# FAIO_Multiplexer.net
KiCad netlist of a schematic drawn in EAGLE
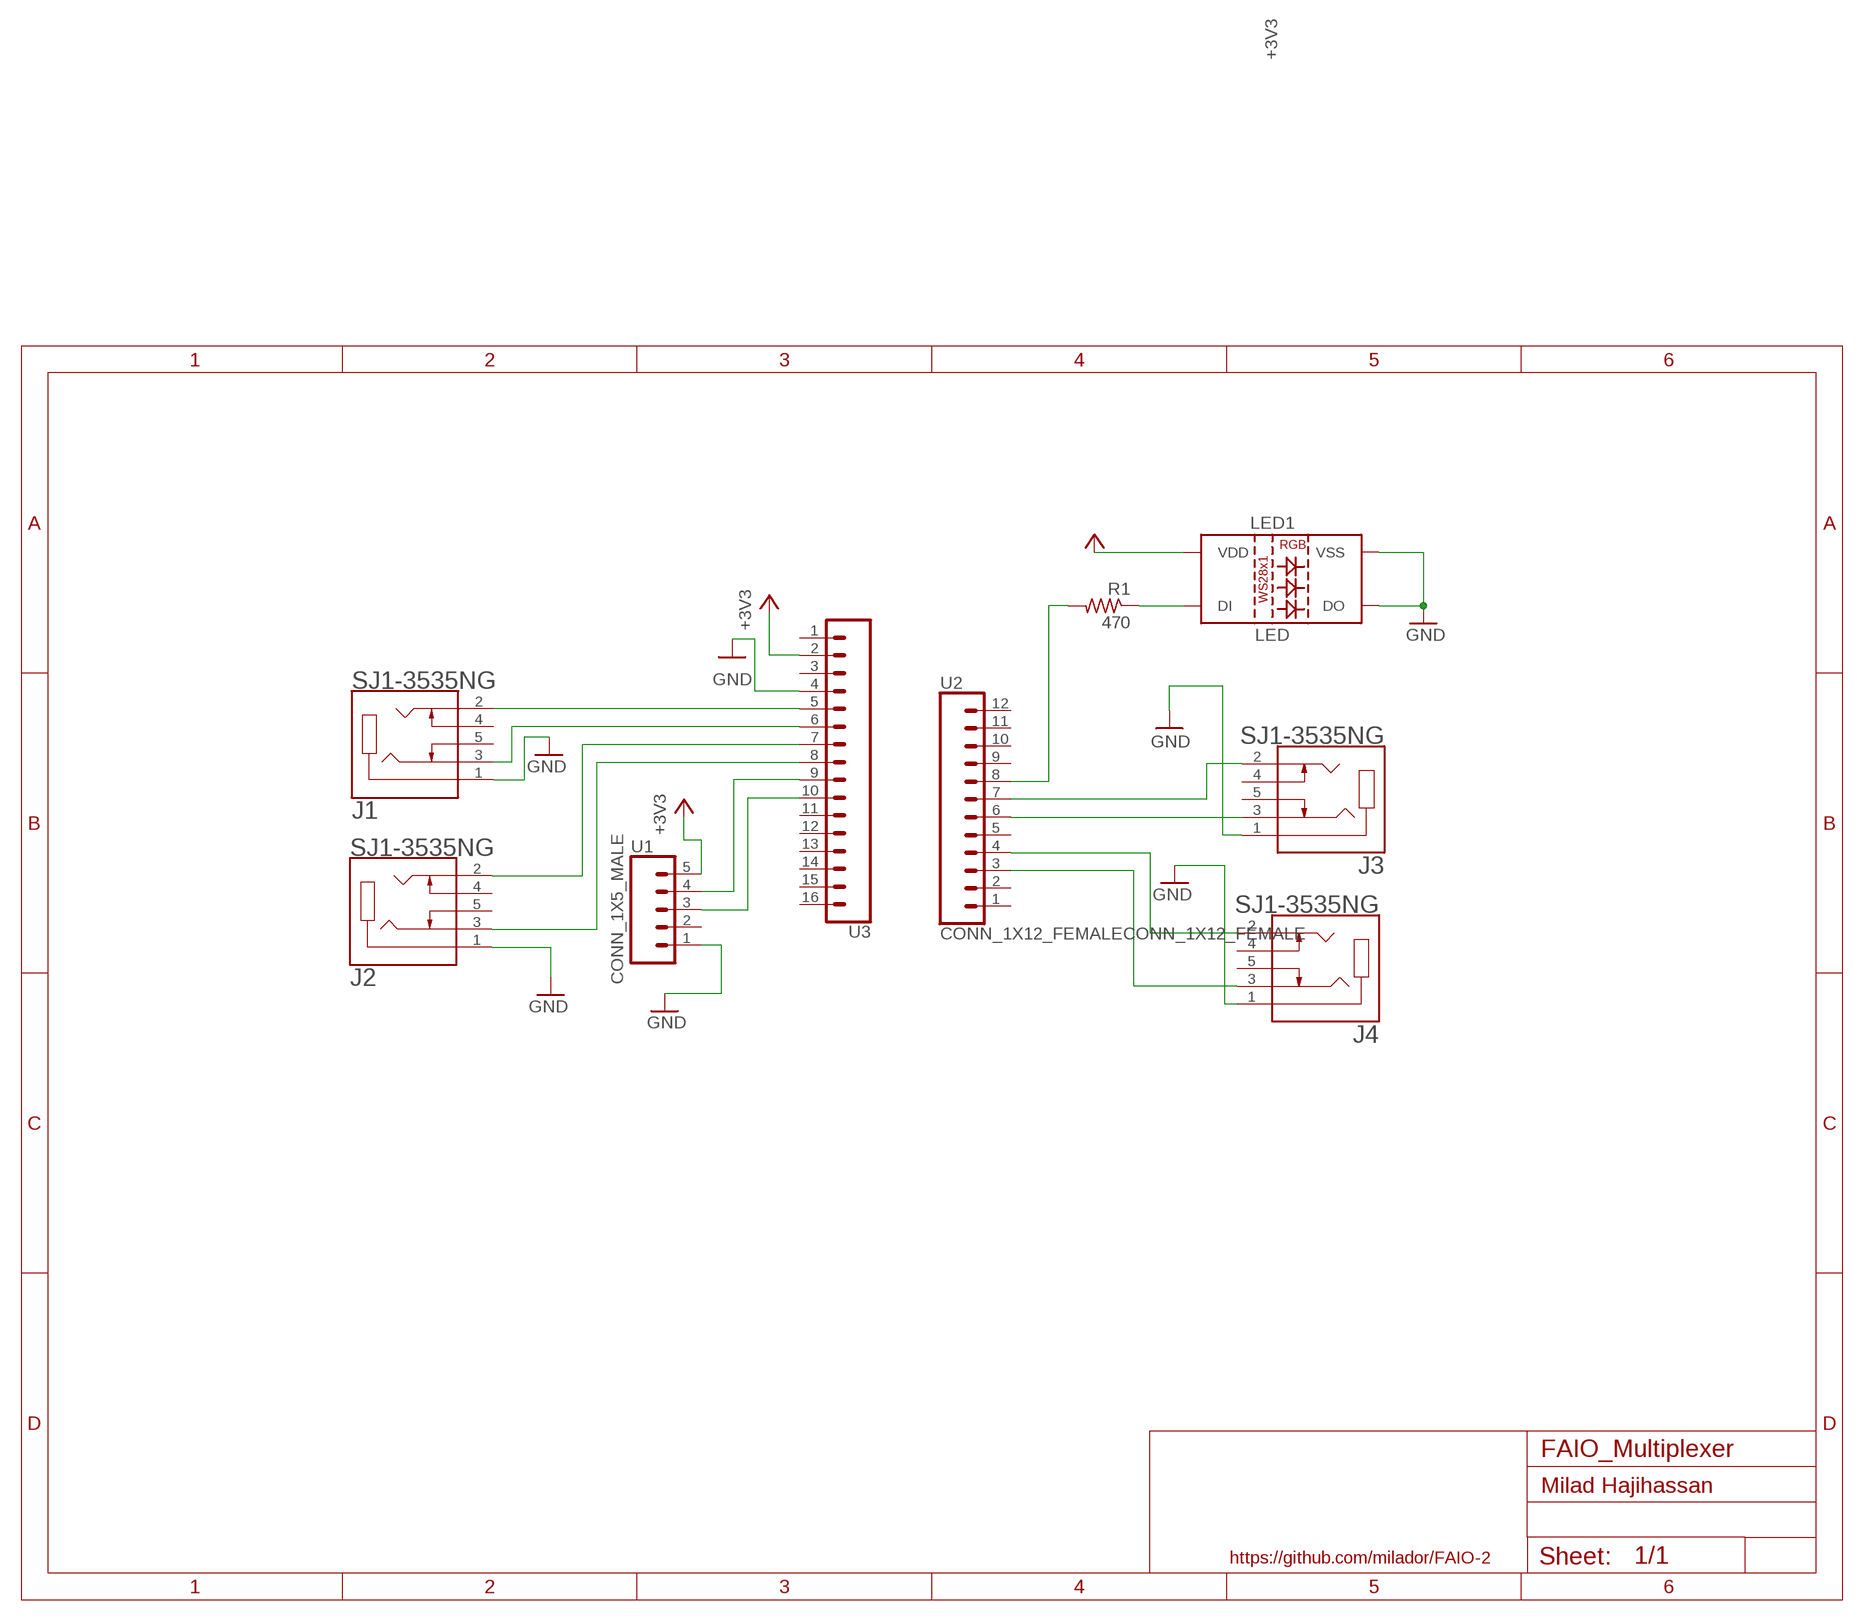
[diagram p0: schematic, sheet 1]

(export (version "E")
  (design (tool "Eeschema 10.0.6"))
  (components
    (comp (ref "J1")
      (value "SJ1-3535NG")
      (footprint "eagle-import:CUI_SJ1-3535NG")
      (fields (field (name "MANUFACTURER") "CUI"))
      (libsource (lib "eagle-import") (part "SJ1-3535NG"))
    )
    (comp (ref "J2")
      (value "SJ1-3535NG")
      (footprint "eagle-import:CUI_SJ1-3535NG")
      (fields (field (name "MANUFACTURER") "CUI"))
      (libsource (lib "eagle-import") (part "SJ1-3535NG"))
    )
    (comp (ref "J3")
      (value "SJ1-3535NG")
      (footprint "eagle-import:CUI_SJ1-3535NG")
      (fields (field (name "MANUFACTURER") "CUI"))
      (libsource (lib "eagle-import") (part "SJ1-3535NG"))
    )
    (comp (ref "J4")
      (value "SJ1-3535NG")
      (footprint "eagle-import:CUI_SJ1-3535NG")
      (fields (field (name "MANUFACTURER") "CUI"))
      (libsource (lib "eagle-import") (part "SJ1-3535NG"))
    )
    (comp (ref "LED1")
      (value "LED")
      (footprint "eagle-import:NEOPIXELS-5MM")
      (libsource (lib "eagle-import") (part "NEOPIXELS-5MM"))
    )
    (comp (ref "R1")
      (value "470")
      (footprint "eagle-import:0204_7")
      (libsource (lib "eagle-import") (part "R-US_0204/7"))
    )
    (comp (ref "U1")
      (value "CONN_1X5_MALE")
      (footprint "eagle-import:CONN_1X5")
      (libsource (lib "eagle-import") (part "CONN_1X5_MALE"))
    )
    (comp (ref "U2")
      (value "CONN_1X12_FEMALECONN_1X12_FEMALE")
      (footprint "eagle-import:CONN_1X12")
      (libsource (lib "eagle-import") (part "CONN_1X12_FEMALECONN_1X12_FEMALE"))
    )
    (comp (ref "U3")
      (value "CONN_1X16_FEMALECONN_1X16_FEMALE")
      (footprint "eagle-import:CONN_1X16")
      (libsource (lib "eagle-import") (part "CONN_1X16_FEMALECONN_1X16_FEMALE"))
    )
  )
  (nets
    (net (code "1") (name "+3V3") (class "Default")
      (node (ref "LED1") (pin "2") (pinfunction "VDD_2") (pintype "bidirectional"))
      (node (ref "U1") (pin "5") (pinfunction "5_5") (pintype "passive"))
      (node (ref "U3") (pin "2") (pinfunction "2_2") (pintype "passive"))
    )
    (net (code "2") (name "GND") (class "Default")
      (node (ref "J1") (pin "1") (pinfunction "1_1") (pintype "passive"))
      (node (ref "J2") (pin "1") (pinfunction "1_1") (pintype "passive"))
      (node (ref "J3") (pin "1") (pinfunction "1_1") (pintype "passive"))
      (node (ref "J4") (pin "1") (pinfunction "1_1") (pintype "passive"))
      (node (ref "LED1") (pin "3") (pinfunction "VSS_3") (pintype "bidirectional"))
      (node (ref "LED1") (pin "4") (pinfunction "DO_4") (pintype "bidirectional"))
      (node (ref "U1") (pin "1") (pinfunction "1_1") (pintype "passive"))
      (node (ref "U3") (pin "4") (pinfunction "4_4") (pintype "passive"))
    )
    (net (code "3") (name "Net-(J1-Pad2)") (class "Default")
      (node (ref "J1") (pin "2") (pinfunction "2_2") (pintype "passive"))
      (node (ref "U3") (pin "5") (pinfunction "5_5") (pintype "passive"))
    )
    (net (code "4") (name "Net-(J1-Pad3)") (class "Default")
      (node (ref "J1") (pin "3") (pinfunction "3_3") (pintype "passive"))
      (node (ref "U3") (pin "6") (pinfunction "6_6") (pintype "passive"))
    )
    (net (code "5") (name "Net-(J2-Pad2)") (class "Default")
      (node (ref "J2") (pin "2") (pinfunction "2_2") (pintype "passive"))
      (node (ref "U3") (pin "7") (pinfunction "7_7") (pintype "passive"))
    )
    (net (code "6") (name "Net-(J2-Pad3)") (class "Default")
      (node (ref "J2") (pin "3") (pinfunction "3_3") (pintype "passive"))
      (node (ref "U3") (pin "8") (pinfunction "8_8") (pintype "passive"))
    )
    (net (code "7") (name "Net-(J3-Pad2)") (class "Default")
      (node (ref "J3") (pin "2") (pinfunction "2_2") (pintype "passive"))
      (node (ref "U2") (pin "7") (pinfunction "7_7") (pintype "passive"))
    )
    (net (code "8") (name "Net-(J3-Pad3)") (class "Default")
      (node (ref "J3") (pin "3") (pinfunction "3_3") (pintype "passive"))
      (node (ref "U2") (pin "6") (pinfunction "6_6") (pintype "passive"))
    )
    (net (code "9") (name "Net-(J4-Pad2)") (class "Default")
      (node (ref "J4") (pin "2") (pinfunction "2_2") (pintype "passive"))
      (node (ref "U2") (pin "4") (pinfunction "4_4") (pintype "passive"))
    )
    (net (code "10") (name "Net-(J4-Pad3)") (class "Default")
      (node (ref "J4") (pin "3") (pinfunction "3_3") (pintype "passive"))
      (node (ref "U2") (pin "3") (pinfunction "3_3") (pintype "passive"))
    )
    (net (code "11") (name "Net-(LED1-DI)") (class "Default")
      (node (ref "LED1") (pin "1") (pinfunction "DI_1") (pintype "bidirectional"))
      (node (ref "R1") (pin "1") (pinfunction "1_1") (pintype "passive"))
    )
    (net (code "12") (name "Net-(R1-Pad2)") (class "Default")
      (node (ref "R1") (pin "2") (pinfunction "2_2") (pintype "passive"))
      (node (ref "U2") (pin "8") (pinfunction "8_8") (pintype "passive"))
    )
    (net (code "13") (name "Net-(U1-Pad3)") (class "Default")
      (node (ref "U1") (pin "3") (pinfunction "3_3") (pintype "passive"))
      (node (ref "U3") (pin "10") (pinfunction "10_10") (pintype "passive"))
    )
    (net (code "14") (name "Net-(U1-Pad4)") (class "Default")
      (node (ref "U1") (pin "4") (pinfunction "4_4") (pintype "passive"))
      (node (ref "U3") (pin "9") (pinfunction "9_9") (pintype "passive"))
    )
    (net (code "15") (name "unconnected-(J1-Pad4)") (class "Default")
      (node (ref "J1") (pin "4") (pinfunction "4_4") (pintype "passive"))
    )
    (net (code "16") (name "unconnected-(J1-Pad5)") (class "Default")
      (node (ref "J1") (pin "5") (pinfunction "5_5") (pintype "passive"))
    )
    (net (code "17") (name "unconnected-(J2-Pad4)") (class "Default")
      (node (ref "J2") (pin "4") (pinfunction "4_4") (pintype "passive"))
    )
    (net (code "18") (name "unconnected-(J2-Pad5)") (class "Default")
      (node (ref "J2") (pin "5") (pinfunction "5_5") (pintype "passive"))
    )
    (net (code "19") (name "unconnected-(J3-Pad4)") (class "Default")
      (node (ref "J3") (pin "4") (pinfunction "4_4") (pintype "passive"))
    )
    (net (code "20") (name "unconnected-(J3-Pad5)") (class "Default")
      (node (ref "J3") (pin "5") (pinfunction "5_5") (pintype "passive"))
    )
    (net (code "21") (name "unconnected-(J4-Pad4)") (class "Default")
      (node (ref "J4") (pin "4") (pinfunction "4_4") (pintype "passive"))
    )
    (net (code "22") (name "unconnected-(J4-Pad5)") (class "Default")
      (node (ref "J4") (pin "5") (pinfunction "5_5") (pintype "passive"))
    )
    (net (code "23") (name "unconnected-(U1-Pad2)") (class "Default")
      (node (ref "U1") (pin "2") (pinfunction "2_2") (pintype "passive"))
    )
    (net (code "24") (name "unconnected-(U2-Pad1)") (class "Default")
      (node (ref "U2") (pin "1") (pinfunction "1_1") (pintype "passive"))
    )
    (net (code "25") (name "unconnected-(U2-Pad2)") (class "Default")
      (node (ref "U2") (pin "2") (pinfunction "2_2") (pintype "passive"))
    )
    (net (code "26") (name "unconnected-(U2-Pad5)") (class "Default")
      (node (ref "U2") (pin "5") (pinfunction "5_5") (pintype "passive"))
    )
    (net (code "27") (name "unconnected-(U2-Pad9)") (class "Default")
      (node (ref "U2") (pin "9") (pinfunction "9_9") (pintype "passive"))
    )
    (net (code "28") (name "unconnected-(U2-Pad10)") (class "Default")
      (node (ref "U2") (pin "10") (pinfunction "10_10") (pintype "passive"))
    )
    (net (code "29") (name "unconnected-(U2-Pad11)") (class "Default")
      (node (ref "U2") (pin "11") (pinfunction "11_11") (pintype "passive"))
    )
    (net (code "30") (name "unconnected-(U2-Pad12)") (class "Default")
      (node (ref "U2") (pin "12") (pinfunction "12_12") (pintype "passive"))
    )
    (net (code "31") (name "unconnected-(U3-Pad1)") (class "Default")
      (node (ref "U3") (pin "1") (pinfunction "1_1") (pintype "passive"))
    )
    (net (code "32") (name "unconnected-(U3-Pad3)") (class "Default")
      (node (ref "U3") (pin "3") (pinfunction "3_3") (pintype "passive"))
    )
    (net (code "33") (name "unconnected-(U3-Pad11)") (class "Default")
      (node (ref "U3") (pin "11") (pinfunction "11_11") (pintype "passive"))
    )
    (net (code "34") (name "unconnected-(U3-Pad12)") (class "Default")
      (node (ref "U3") (pin "12") (pinfunction "12_12") (pintype "passive"))
    )
    (net (code "35") (name "unconnected-(U3-Pad13)") (class "Default")
      (node (ref "U3") (pin "13") (pinfunction "13_13") (pintype "passive"))
    )
    (net (code "36") (name "unconnected-(U3-Pad14)") (class "Default")
      (node (ref "U3") (pin "14") (pinfunction "14_14") (pintype "passive"))
    )
    (net (code "37") (name "unconnected-(U3-Pad15)") (class "Default")
      (node (ref "U3") (pin "15") (pinfunction "15_15") (pintype "passive"))
    )
    (net (code "38") (name "unconnected-(U3-Pad16)") (class "Default")
      (node (ref "U3") (pin "16") (pinfunction "16_16") (pintype "passive"))
    )
  )
)
